# UCC14240_Test_Board.net
KiCad netlist of a schematic drawn in Altium Designer
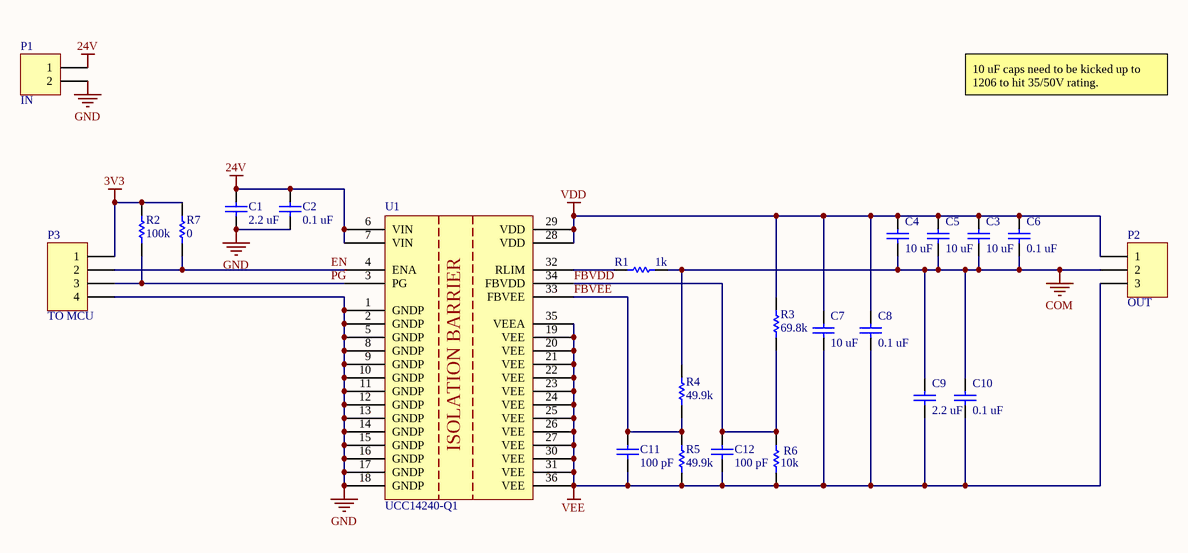
[diagram p0: UCC14240 Test Board.SchDoc]

(export (version "E")
  (design (tool "Eeschema 10.0.6"))
  (components
    (comp (ref "C1")
      (value "2.2 uF")
      (footprint "0805 - Capacitor")
      (description "Nonpolarized Capacitor")
      (fields
        (field (name "MANUFACTURER") "Samsung")
        (field (name "MANUFACTURER PART NUMBER") "CL21A225KBFNNNE")
      )
      (libsource (lib "General") (part "Capacitor - Nonpolarized"))
    )
    (comp (ref "C2")
      (value "0.1 uF")
      (footprint "0805 - Capacitor")
      (description "Nonpolarized Capacitor")
      (fields
        (field (name "MANUFACTURER") "Yageo")
        (field (name "MANUFACTURER PART NUMBER") "CC0805KRX7R9BB104")
      )
      (libsource (lib "General") (part "Capacitor - Nonpolarized"))
    )
    (comp (ref "C3")
      (value "10 uF")
      (footprint "0805 - Capacitor")
      (description "Nonpolarized Capacitor")
      (fields
        (field (name "MANUFACTURER") "Samsung")
        (field (name "MANUFACTURER PART NUMBER") "CL31A106MBHNNNE")
      )
      (libsource (lib "General") (part "Capacitor - Nonpolarized"))
    )
    (comp (ref "C4")
      (value "10 uF")
      (footprint "0805 - Capacitor")
      (description "Nonpolarized Capacitor")
      (fields
        (field (name "MANUFACTURER") "Samsung")
        (field (name "MANUFACTURER PART NUMBER") "CL31A106MBHNNNE")
      )
      (libsource (lib "General") (part "Capacitor - Nonpolarized"))
    )
    (comp (ref "C5")
      (value "10 uF")
      (footprint "0805 - Capacitor")
      (description "Nonpolarized Capacitor")
      (fields
        (field (name "MANUFACTURER") "Samsung")
        (field (name "MANUFACTURER PART NUMBER") "CL31A106MBHNNNE")
      )
      (libsource (lib "General") (part "Capacitor - Nonpolarized"))
    )
    (comp (ref "C6")
      (value "0.1 uF")
      (footprint "0805 - Capacitor")
      (description "Nonpolarized Capacitor")
      (fields
        (field (name "MANUFACTURER") "Yageo")
        (field (name "MANUFACTURER PART NUMBER") "CC0805KRX7R9BB104")
      )
      (libsource (lib "General") (part "Capacitor - Nonpolarized"))
    )
    (comp (ref "C7")
      (value "10 uF")
      (footprint "0805 - Capacitor")
      (description "Nonpolarized Capacitor")
      (fields
        (field (name "MANUFACTURER") "Samsung")
        (field (name "MANUFACTURER PART NUMBER") "CL31A106MBHNNNE")
      )
      (libsource (lib "General") (part "Capacitor - Nonpolarized"))
    )
    (comp (ref "C8")
      (value "0.1 uF")
      (footprint "0805 - Capacitor")
      (description "Nonpolarized Capacitor")
      (fields
        (field (name "MANUFACTURER") "Yageo")
        (field (name "MANUFACTURER PART NUMBER") "CC0805KRX7R9BB104")
      )
      (libsource (lib "General") (part "Capacitor - Nonpolarized"))
    )
    (comp (ref "C9")
      (value "2.2 uF")
      (footprint "0805 - Capacitor")
      (description "Nonpolarized Capacitor")
      (fields
        (field (name "MANUFACTURER") "Samsung")
        (field (name "MANUFACTURER PART NUMBER") "CL21A225KBFNNNE")
      )
      (libsource (lib "General") (part "Capacitor - Nonpolarized"))
    )
    (comp (ref "C10")
      (value "0.1 uF")
      (footprint "0805 - Capacitor")
      (description "Nonpolarized Capacitor")
      (fields
        (field (name "MANUFACTURER") "Yageo")
        (field (name "MANUFACTURER PART NUMBER") "CC0805KRX7R9BB104")
      )
      (libsource (lib "General") (part "Capacitor - Nonpolarized"))
    )
    (comp (ref "C11")
      (value "100 pF")
      (footprint "0603 - Capacitor")
      (description "Nonpolarized Capacitor")
      (fields
        (field (name "MANUFACTURER") "Yageo")
        (field (name "MANUFACTURER PART NUMBER") "CC0603JRNPO9BN101")
      )
      (libsource (lib "General") (part "Capacitor - Nonpolarized"))
    )
    (comp (ref "C12")
      (value "100 pF")
      (footprint "0603 - Capacitor")
      (description "Nonpolarized Capacitor")
      (fields
        (field (name "MANUFACTURER") "Yageo")
        (field (name "MANUFACTURER PART NUMBER") "CC0603JRNPO9BN101")
      )
      (libsource (lib "General") (part "Capacitor - Nonpolarized"))
    )
    (comp (ref "P1")
      (value "IN")
      (footprint "HDR1X2")
      (description "1x2 Pin Header")
      (libsource (lib "GeneralConnectors") (part "1x2 Header"))
    )
    (comp (ref "P2")
      (value "OUT")
      (footprint "HDR1X3")
      (description "1x3 Pin Header")
      (libsource (lib "GeneralConnectors") (part "1x3 Header"))
    )
    (comp (ref "P3")
      (value "TO MCU")
      (footprint "HDR1X4")
      (description "1x4 Pin Header")
      (libsource (lib "GeneralConnectors") (part "1x4 Header"))
    )
    (comp (ref "R1")
      (value "1k")
      (footprint "0805 - Resistor")
      (description "Resistor")
      (fields
        (field (name "MANUFACTURER PART NUMBER") "RNCP0805FTD1K00")
        (field (name "MANUFACTURER") "Stackpole")
      )
      (libsource (lib "General") (part "Resistor"))
    )
    (comp (ref "R2")
      (value "100k")
      (footprint "0603 - Resistor")
      (description "Resistor")
      (fields
        (field (name "MANUFACTURER PART NUMBER") "RC0603FR-07100KL")
        (field (name "MANUFACTURER") "Yageo")
      )
      (libsource (lib "General") (part "Resistor"))
    )
    (comp (ref "R3")
      (value "69.8k")
      (footprint "0603 - Resistor")
      (description "Resistor")
      (fields
        (field (name "MANUFACTURER PART NUMBER") "RC0603FR-0769K8L")
        (field (name "MANUFACTURER") "Yageo")
      )
      (libsource (lib "General") (part "Resistor"))
    )
    (comp (ref "R4")
      (value "49.9k")
      (footprint "0603 - Resistor")
      (description "Resistor")
      (fields
        (field (name "MANUFACTURER PART NUMBER") "RMCF0603FG49K9")
        (field (name "MANUFACTURER") "Stackpole")
      )
      (libsource (lib "General") (part "Resistor"))
    )
    (comp (ref "R5")
      (value "49.9k")
      (footprint "0603 - Resistor")
      (description "Resistor")
      (fields
        (field (name "MANUFACTURER PART NUMBER") "RMCF0603FG49K9")
        (field (name "MANUFACTURER") "Stackpole")
      )
      (libsource (lib "General") (part "Resistor"))
    )
    (comp (ref "R6")
      (value "10k")
      (footprint "0603 - Resistor")
      (description "Resistor")
      (fields
        (field (name "MANUFACTURER PART NUMBER") "RC0603FR-0710KL")
        (field (name "MANUFACTURER") "Yageo")
      )
      (libsource (lib "General") (part "Resistor"))
    )
    (comp (ref "R7")
      (value "0")
      (footprint "0603 - Resistor")
      (description "Resistor")
      (fields
        (field (name "MANUFACTURER PART NUMBER") "CR0603-J/-000ELF")
        (field (name "MANUFACTURER") "Bourns")
      )
      (libsource (lib "General") (part "Resistor"))
    )
    (comp (ref "U1")
      (value "UCC14240-Q1")
      (footprint "MC:SOP65P1020X355-36N")
      (description "Isolated DC/DC Converter with Integrated Transformer")
      (fields (field (name "MANUFACTURER") "Texas Instruments"))
      (libsource (lib "MC") (part "UCC14240-Q1"))
    )
  )
  (nets
    (net (code "1") (name "/EN") (class "Default")
      (node (ref "P3") (pin "2") (pinfunction "2_2") (pintype "passive"))
      (node (ref "R7") (pin "1") (pinfunction "1_1") (pintype "passive"))
      (node (ref "U1") (pin "4") (pinfunction "ENA_4") (pintype "passive"))
    )
    (net (code "2") (name "/FBVDD") (class "Default")
      (node (ref "C12") (pin "2") (pinfunction "2_2") (pintype "passive"))
      (node (ref "R3") (pin "1") (pinfunction "1_1") (pintype "passive"))
      (node (ref "R6") (pin "2") (pinfunction "2_2") (pintype "passive"))
      (node (ref "U1") (pin "34") (pinfunction "FBVDD_34") (pintype "passive"))
    )
    (net (code "3") (name "/FBVEE") (class "Default")
      (node (ref "C11") (pin "2") (pinfunction "2_2") (pintype "passive"))
      (node (ref "R4") (pin "1") (pinfunction "1_1") (pintype "passive"))
      (node (ref "R5") (pin "2") (pinfunction "2_2") (pintype "passive"))
      (node (ref "U1") (pin "33") (pinfunction "FBVEE_33") (pintype "passive"))
    )
    (net (code "4") (name "/~{PG}") (class "Default")
      (node (ref "P3") (pin "3") (pinfunction "3_3") (pintype "passive"))
      (node (ref "R2") (pin "1") (pinfunction "1_1") (pintype "passive"))
      (node (ref "U1") (pin "3") (pinfunction "PG_3") (pintype "passive"))
    )
    (net (code "5") (name "3V3") (class "Default")
      (node (ref "P3") (pin "1") (pinfunction "1_1") (pintype "passive"))
      (node (ref "R2") (pin "2") (pinfunction "2_2") (pintype "passive"))
      (node (ref "R7") (pin "2") (pinfunction "2_2") (pintype "passive"))
    )
    (net (code "6") (name "24V") (class "Default")
      (node (ref "C1") (pin "2") (pinfunction "2_2") (pintype "passive"))
      (node (ref "C2") (pin "2") (pinfunction "2_2") (pintype "passive"))
      (node (ref "P1") (pin "1") (pinfunction "1_1") (pintype "passive"))
      (node (ref "U1") (pin "6") (pinfunction "VIN_6") (pintype "passive"))
      (node (ref "U1") (pin "7") (pinfunction "VIN_7") (pintype "passive"))
    )
    (net (code "7") (name "COM") (class "Default")
      (node (ref "C10") (pin "2") (pinfunction "2_2") (pintype "passive"))
      (node (ref "C3") (pin "1") (pinfunction "1_1") (pintype "passive"))
      (node (ref "C4") (pin "1") (pinfunction "1_1") (pintype "passive"))
      (node (ref "C5") (pin "1") (pinfunction "1_1") (pintype "passive"))
      (node (ref "C6") (pin "1") (pinfunction "1_1") (pintype "passive"))
      (node (ref "C9") (pin "2") (pinfunction "2_2") (pintype "passive"))
      (node (ref "P2") (pin "2") (pinfunction "2_2") (pintype "passive"))
      (node (ref "R1") (pin "2") (pinfunction "2_2") (pintype "passive"))
      (node (ref "R4") (pin "2") (pinfunction "2_2") (pintype "passive"))
    )
    (net (code "8") (name "GND") (class "Default")
      (node (ref "C1") (pin "1") (pinfunction "1_1") (pintype "passive"))
      (node (ref "C2") (pin "1") (pinfunction "1_1") (pintype "passive"))
      (node (ref "P1") (pin "2") (pinfunction "2_2") (pintype "passive"))
      (node (ref "P3") (pin "4") (pinfunction "4_4") (pintype "passive"))
      (node (ref "U1") (pin "1") (pinfunction "GNDP_1") (pintype "passive"))
      (node (ref "U1") (pin "10") (pinfunction "GNDP_10") (pintype "passive"))
      (node (ref "U1") (pin "11") (pinfunction "GNDP_11") (pintype "passive"))
      (node (ref "U1") (pin "12") (pinfunction "GNDP_12") (pintype "passive"))
      (node (ref "U1") (pin "13") (pinfunction "GNDP_13") (pintype "passive"))
      (node (ref "U1") (pin "14") (pinfunction "GNDP_14") (pintype "passive"))
      (node (ref "U1") (pin "15") (pinfunction "GNDP_15") (pintype "passive"))
      (node (ref "U1") (pin "16") (pinfunction "GNDP_16") (pintype "passive"))
      (node (ref "U1") (pin "17") (pinfunction "GNDP_17") (pintype "passive"))
      (node (ref "U1") (pin "18") (pinfunction "GNDP_18") (pintype "passive"))
      (node (ref "U1") (pin "2") (pinfunction "GNDP_2") (pintype "passive"))
      (node (ref "U1") (pin "5") (pinfunction "GNDP_5") (pintype "passive"))
      (node (ref "U1") (pin "8") (pinfunction "GNDP_8") (pintype "passive"))
      (node (ref "U1") (pin "9") (pinfunction "GNDP_9") (pintype "passive"))
    )
    (net (code "9") (name "Net-(U1-RLIM)") (class "Default")
      (node (ref "R1") (pin "1") (pinfunction "1_1") (pintype "passive"))
      (node (ref "U1") (pin "32") (pinfunction "RLIM_32") (pintype "passive"))
    )
    (net (code "10") (name "VDD") (class "Default")
      (node (ref "C3") (pin "2") (pinfunction "2_2") (pintype "passive"))
      (node (ref "C4") (pin "2") (pinfunction "2_2") (pintype "passive"))
      (node (ref "C5") (pin "2") (pinfunction "2_2") (pintype "passive"))
      (node (ref "C6") (pin "2") (pinfunction "2_2") (pintype "passive"))
      (node (ref "C7") (pin "2") (pinfunction "2_2") (pintype "passive"))
      (node (ref "C8") (pin "2") (pinfunction "2_2") (pintype "passive"))
      (node (ref "P2") (pin "1") (pinfunction "1_1") (pintype "passive"))
      (node (ref "R3") (pin "2") (pinfunction "2_2") (pintype "passive"))
      (node (ref "U1") (pin "28") (pinfunction "VDD_28") (pintype "passive"))
      (node (ref "U1") (pin "29") (pinfunction "VDD_29") (pintype "passive"))
    )
    (net (code "11") (name "VEE") (class "Default")
      (node (ref "C10") (pin "1") (pinfunction "1_1") (pintype "passive"))
      (node (ref "C11") (pin "1") (pinfunction "1_1") (pintype "passive"))
      (node (ref "C12") (pin "1") (pinfunction "1_1") (pintype "passive"))
      (node (ref "C7") (pin "1") (pinfunction "1_1") (pintype "passive"))
      (node (ref "C8") (pin "1") (pinfunction "1_1") (pintype "passive"))
      (node (ref "C9") (pin "1") (pinfunction "1_1") (pintype "passive"))
      (node (ref "P2") (pin "3") (pinfunction "3_3") (pintype "passive"))
      (node (ref "R5") (pin "1") (pinfunction "1_1") (pintype "passive"))
      (node (ref "R6") (pin "1") (pinfunction "1_1") (pintype "passive"))
      (node (ref "U1") (pin "19") (pinfunction "VEE_19") (pintype "passive"))
      (node (ref "U1") (pin "20") (pinfunction "VEE_20") (pintype "passive"))
      (node (ref "U1") (pin "21") (pinfunction "VEE_21") (pintype "passive"))
      (node (ref "U1") (pin "22") (pinfunction "VEE_22") (pintype "passive"))
      (node (ref "U1") (pin "23") (pinfunction "VEE_23") (pintype "passive"))
      (node (ref "U1") (pin "24") (pinfunction "VEE_24") (pintype "passive"))
      (node (ref "U1") (pin "25") (pinfunction "VEE_25") (pintype "passive"))
      (node (ref "U1") (pin "26") (pinfunction "VEE_26") (pintype "passive"))
      (node (ref "U1") (pin "27") (pinfunction "VEE_27") (pintype "passive"))
      (node (ref "U1") (pin "30") (pinfunction "VEE_30") (pintype "passive"))
      (node (ref "U1") (pin "31") (pinfunction "VEE_31") (pintype "passive"))
      (node (ref "U1") (pin "35") (pinfunction "VEEA_35") (pintype "passive"))
      (node (ref "U1") (pin "36") (pinfunction "VEE_36") (pintype "passive"))
    )
  )
)
